# hdmi_receiver.net
KiCad netlist of a schematic drawn in EAGLE
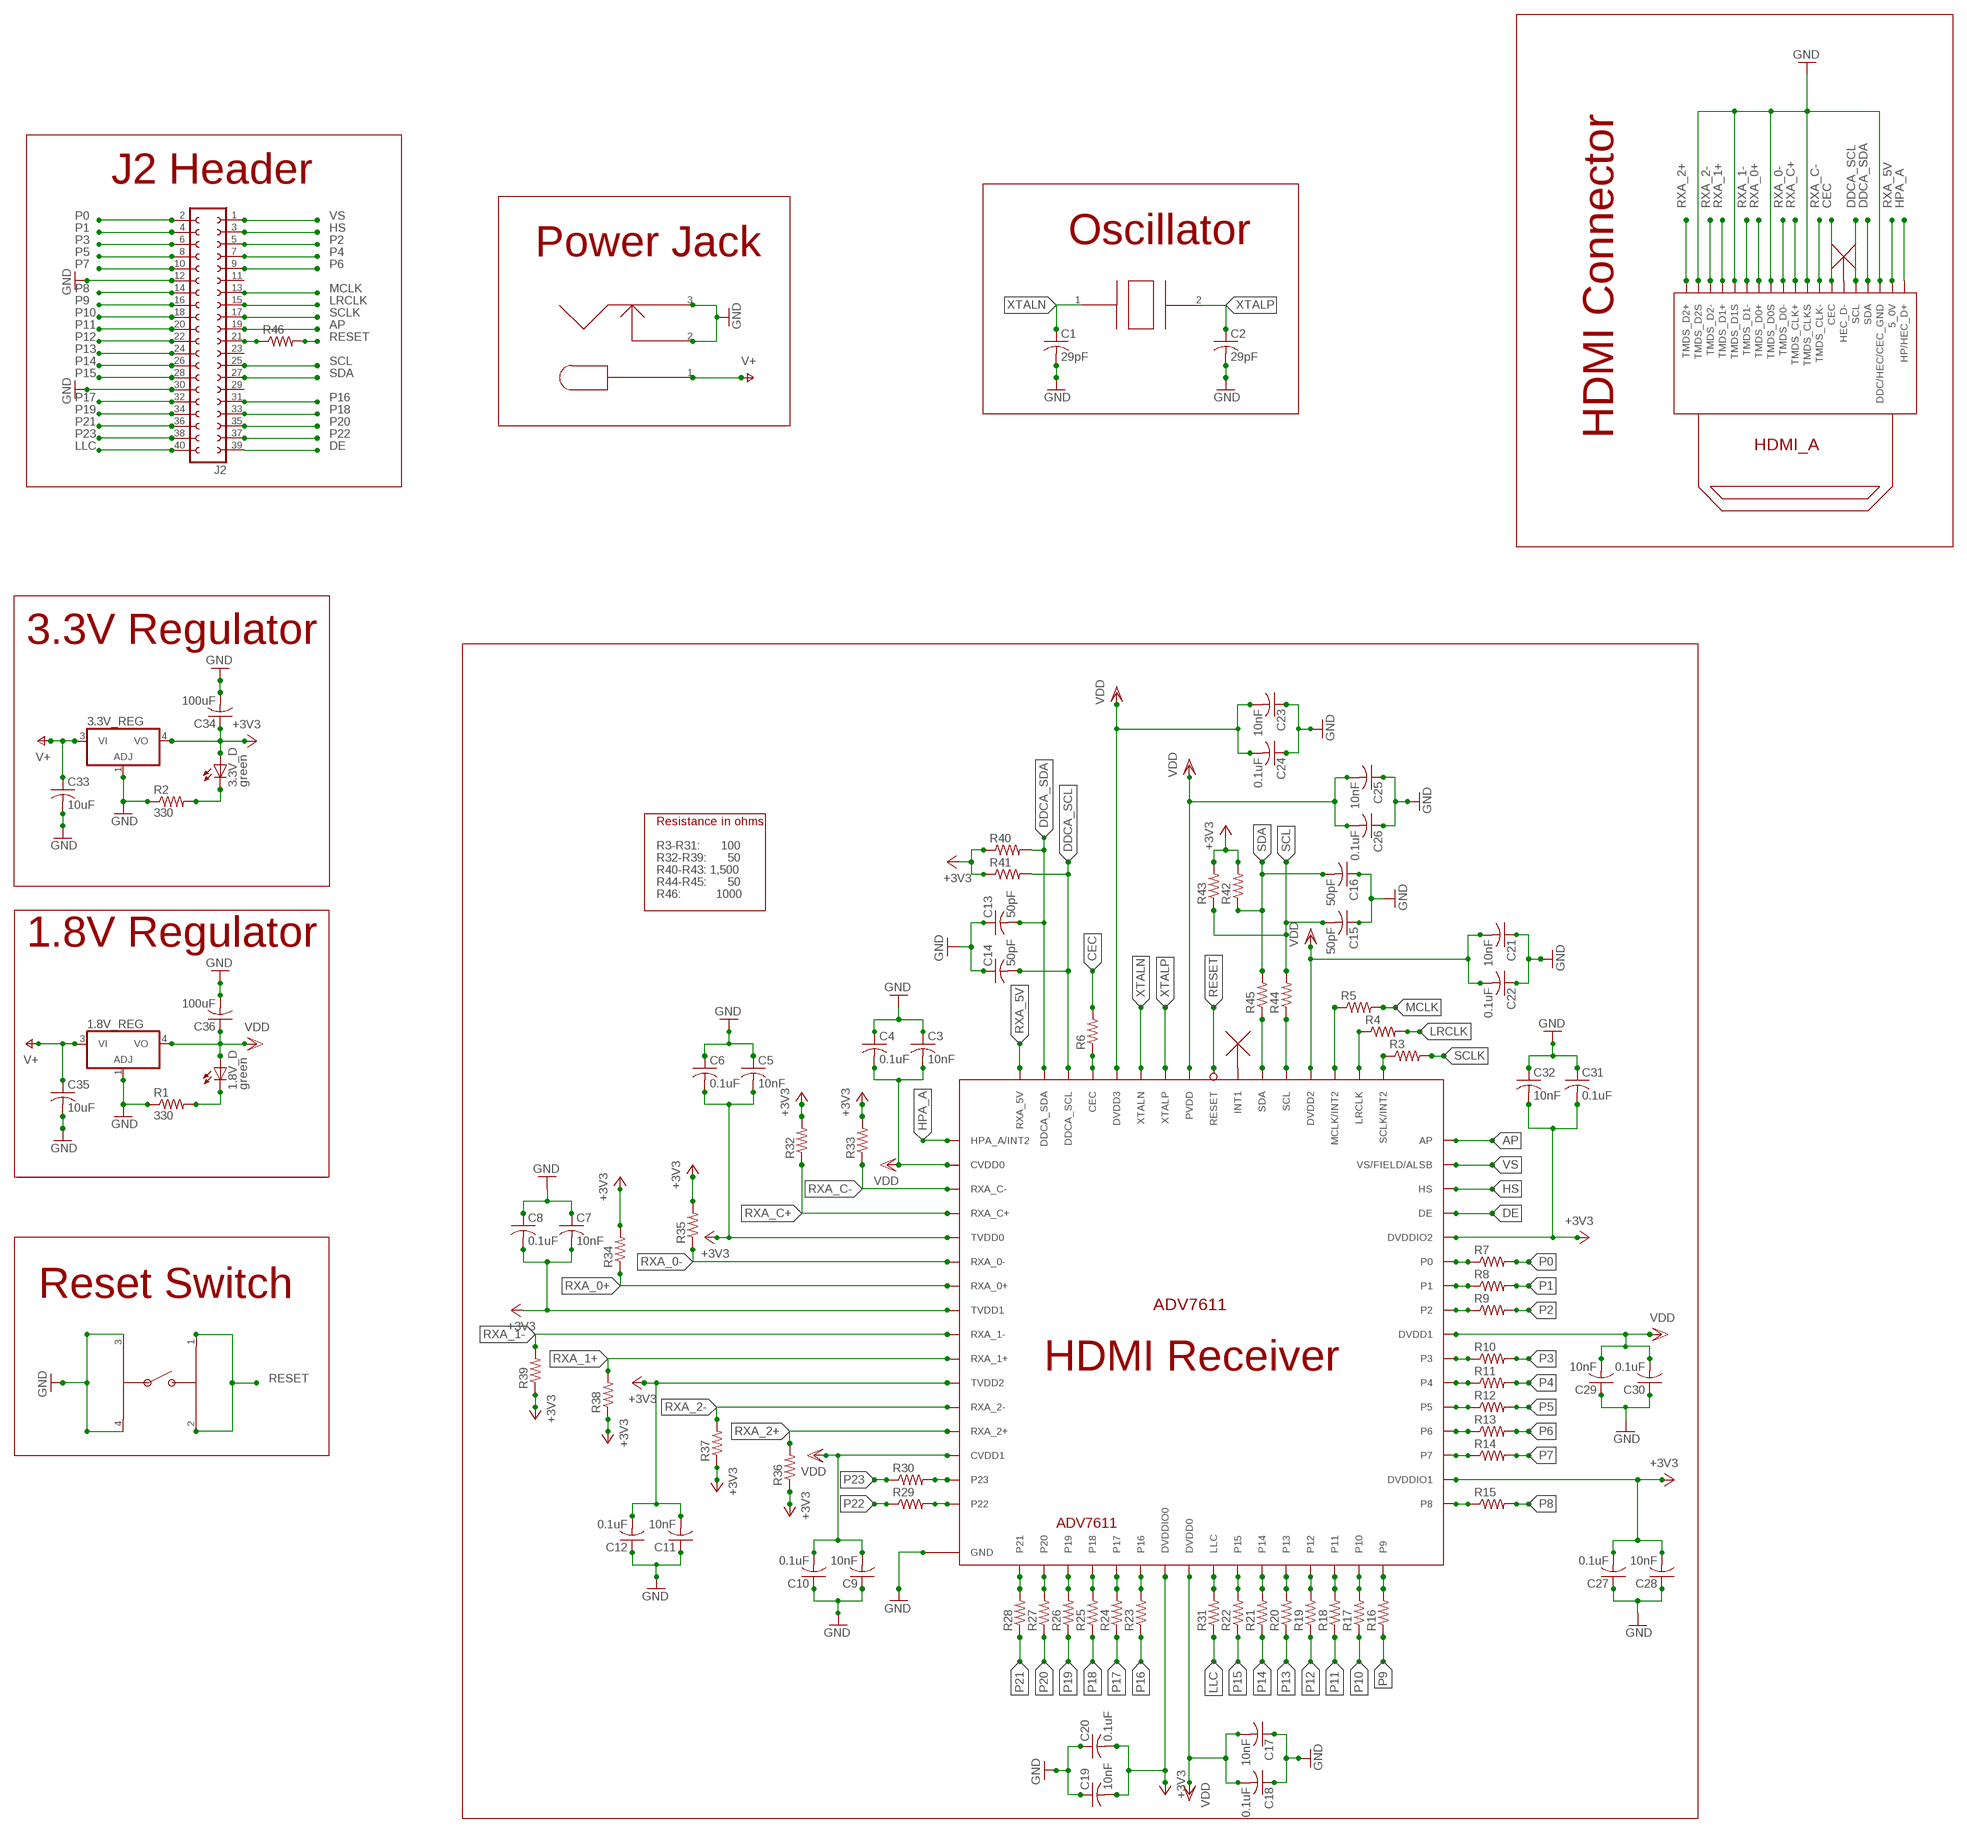
[diagram p0: schematic, sheet 1]

(export (version "E")
  (design (tool "Eeschema 10.0.6"))
  (components
    (comp (ref "1.8V_D")
      (value "green")
      (footprint "eagle-import:LED5MM")
      (libsource (lib "eagle-import") (part "LED5MM"))
    )
    (comp (ref "1.8V_REG")
      (value "317EMP")
      (footprint "eagle-import:SOT223")
      (libsource (lib "eagle-import") (part "317EMP"))
    )
    (comp (ref "3.3V_D")
      (value "green")
      (footprint "eagle-import:LED5MM")
      (libsource (lib "eagle-import") (part "LED5MM"))
    )
    (comp (ref "3.3V_REG")
      (value "317EMP")
      (footprint "eagle-import:SOT223")
      (libsource (lib "eagle-import") (part "317EMP"))
    )
    (comp (ref "ADV7611")
      (value "ADV7611")
      (footprint "eagle-import:LQFP-ST-64-2")
      (libsource (lib "eagle-import") (part "ADV7611"))
    )
    (comp (ref "C1")
      (value "29pF")
      (footprint "eagle-import:C1210")
      (libsource (lib "eagle-import") (part "C-USC1210"))
    )
    (comp (ref "C2")
      (value "29pF")
      (footprint "eagle-import:C1210")
      (libsource (lib "eagle-import") (part "C-USC1210"))
    )
    (comp (ref "C3")
      (value "10nF")
      (footprint "eagle-import:C0603")
      (libsource (lib "eagle-import") (part "C-USC0603"))
    )
    (comp (ref "C4")
      (value "0.1uF")
      (footprint "eagle-import:C0603")
      (libsource (lib "eagle-import") (part "C-USC0603"))
    )
    (comp (ref "C5")
      (value "10nF")
      (footprint "eagle-import:C0603")
      (libsource (lib "eagle-import") (part "C-USC0603"))
    )
    (comp (ref "C6")
      (value "0.1uF")
      (footprint "eagle-import:C0603")
      (libsource (lib "eagle-import") (part "C-USC0603"))
    )
    (comp (ref "C7")
      (value "10nF")
      (footprint "eagle-import:C0603")
      (libsource (lib "eagle-import") (part "C-USC0603"))
    )
    (comp (ref "C8")
      (value "0.1uF")
      (footprint "eagle-import:C0603")
      (libsource (lib "eagle-import") (part "C-USC0603"))
    )
    (comp (ref "C9")
      (value "10nF")
      (footprint "eagle-import:C0603")
      (libsource (lib "eagle-import") (part "C-USC0603"))
    )
    (comp (ref "C10")
      (value "0.1uF")
      (footprint "eagle-import:C0603")
      (libsource (lib "eagle-import") (part "C-USC0603"))
    )
    (comp (ref "C11")
      (value "10nF")
      (footprint "eagle-import:C0603")
      (libsource (lib "eagle-import") (part "C-USC0603"))
    )
    (comp (ref "C12")
      (value "0.1uF")
      (footprint "eagle-import:C0603")
      (libsource (lib "eagle-import") (part "C-USC0603"))
    )
    (comp (ref "C13")
      (value "50pF")
      (footprint "eagle-import:C0603")
      (libsource (lib "eagle-import") (part "C-USC0603"))
    )
    (comp (ref "C14")
      (value "50pF")
      (footprint "eagle-import:C0603")
      (libsource (lib "eagle-import") (part "C-USC0603"))
    )
    (comp (ref "C15")
      (value "50pF")
      (footprint "eagle-import:C0603")
      (libsource (lib "eagle-import") (part "C-USC0603"))
    )
    (comp (ref "C16")
      (value "50pF")
      (footprint "eagle-import:C0603")
      (libsource (lib "eagle-import") (part "C-USC0603"))
    )
    (comp (ref "C17")
      (value "10nF")
      (footprint "eagle-import:C0603")
      (libsource (lib "eagle-import") (part "C-USC0603"))
    )
    (comp (ref "C18")
      (value "0.1uF")
      (footprint "eagle-import:C0603")
      (libsource (lib "eagle-import") (part "C-USC0603"))
    )
    (comp (ref "C19")
      (value "10nF")
      (footprint "eagle-import:C0603")
      (libsource (lib "eagle-import") (part "C-USC0603"))
    )
    (comp (ref "C20")
      (value "0.1uF")
      (footprint "eagle-import:C0603")
      (libsource (lib "eagle-import") (part "C-USC0603"))
    )
    (comp (ref "C21")
      (value "10nF")
      (footprint "eagle-import:C0603")
      (libsource (lib "eagle-import") (part "C-USC0603"))
    )
    (comp (ref "C22")
      (value "0.1uF")
      (footprint "eagle-import:C0603")
      (libsource (lib "eagle-import") (part "C-USC0603"))
    )
    (comp (ref "C23")
      (value "10nF")
      (footprint "eagle-import:C0603")
      (libsource (lib "eagle-import") (part "C-USC0603"))
    )
    (comp (ref "C24")
      (value "0.1uF")
      (footprint "eagle-import:C0603")
      (libsource (lib "eagle-import") (part "C-USC0603"))
    )
    (comp (ref "C25")
      (value "10nF")
      (footprint "eagle-import:C0603")
      (libsource (lib "eagle-import") (part "C-USC0603"))
    )
    (comp (ref "C26")
      (value "0.1uF")
      (footprint "eagle-import:C0603")
      (libsource (lib "eagle-import") (part "C-USC0603"))
    )
    (comp (ref "C27")
      (value "0.1uF")
      (footprint "eagle-import:C0603")
      (libsource (lib "eagle-import") (part "C-USC0603"))
    )
    (comp (ref "C28")
      (value "10nF")
      (footprint "eagle-import:C0603")
      (libsource (lib "eagle-import") (part "C-USC0603"))
    )
    (comp (ref "C29")
      (value "10nF")
      (footprint "eagle-import:C0603")
      (libsource (lib "eagle-import") (part "C-USC0603"))
    )
    (comp (ref "C30")
      (value "0.1uF")
      (footprint "eagle-import:C0603")
      (libsource (lib "eagle-import") (part "C-USC0603"))
    )
    (comp (ref "C31")
      (value "0.1uF")
      (footprint "eagle-import:C0603")
      (libsource (lib "eagle-import") (part "C-USC0603"))
    )
    (comp (ref "C32")
      (value "10nF")
      (footprint "eagle-import:C0603")
      (libsource (lib "eagle-import") (part "C-USC0603"))
    )
    (comp (ref "C33")
      (value "10uF")
      (footprint "eagle-import:C0603")
      (libsource (lib "eagle-import") (part "C-USC0603"))
    )
    (comp (ref "C34")
      (value "100uF")
      (footprint "eagle-import:C1206")
      (libsource (lib "eagle-import") (part "C-USC1206"))
    )
    (comp (ref "C35")
      (value "10uF")
      (footprint "eagle-import:C0603")
      (libsource (lib "eagle-import") (part "C-USC0603"))
    )
    (comp (ref "C36")
      (value "100uF")
      (footprint "eagle-import:C1206")
      (libsource (lib "eagle-import") (part "C-USC1206"))
    )
    (comp (ref "J2")
      (value "FE20-2")
      (footprint "eagle-import:FE20-2")
      (libsource (lib "eagle-import") (part "FE20-2"))
    )
    (comp (ref "R1")
      (value "330")
      (footprint "eagle-import:R0603")
      (libsource (lib "eagle-import") (part "R-US_R0603"))
    )
    (comp (ref "R2")
      (value "330")
      (footprint "eagle-import:R0603")
      (libsource (lib "eagle-import") (part "R-US_R0603"))
    )
    (comp (ref "R3")
      (value "R-US_R0603")
      (footprint "eagle-import:R0603")
      (libsource (lib "eagle-import") (part "R-US_R0603"))
    )
    (comp (ref "R4")
      (value "R-US_R0603")
      (footprint "eagle-import:R0603")
      (libsource (lib "eagle-import") (part "R-US_R0603"))
    )
    (comp (ref "R5")
      (value "R-US_R0603")
      (footprint "eagle-import:R0603")
      (libsource (lib "eagle-import") (part "R-US_R0603"))
    )
    (comp (ref "R6")
      (value "R-US_R0603")
      (footprint "eagle-import:R0603")
      (libsource (lib "eagle-import") (part "R-US_R0603"))
    )
    (comp (ref "R7")
      (value "R-US_R0603")
      (footprint "eagle-import:R0603")
      (libsource (lib "eagle-import") (part "R-US_R0603"))
    )
    (comp (ref "R8")
      (value "R-US_R0603")
      (footprint "eagle-import:R0603")
      (libsource (lib "eagle-import") (part "R-US_R0603"))
    )
    (comp (ref "R9")
      (value "R-US_R0603")
      (footprint "eagle-import:R0603")
      (libsource (lib "eagle-import") (part "R-US_R0603"))
    )
    (comp (ref "R10")
      (value "R-US_R0603")
      (footprint "eagle-import:R0603")
      (libsource (lib "eagle-import") (part "R-US_R0603"))
    )
    (comp (ref "R11")
      (value "R-US_R0603")
      (footprint "eagle-import:R0603")
      (libsource (lib "eagle-import") (part "R-US_R0603"))
    )
    (comp (ref "R12")
      (value "R-US_R0603")
      (footprint "eagle-import:R0603")
      (libsource (lib "eagle-import") (part "R-US_R0603"))
    )
    (comp (ref "R13")
      (value "R-US_R0603")
      (footprint "eagle-import:R0603")
      (libsource (lib "eagle-import") (part "R-US_R0603"))
    )
    (comp (ref "R14")
      (value "R-US_R0603")
      (footprint "eagle-import:R0603")
      (libsource (lib "eagle-import") (part "R-US_R0603"))
    )
    (comp (ref "R15")
      (value "R-US_R0603")
      (footprint "eagle-import:R0603")
      (libsource (lib "eagle-import") (part "R-US_R0603"))
    )
    (comp (ref "R16")
      (value "R-US_R0603")
      (footprint "eagle-import:R0603")
      (libsource (lib "eagle-import") (part "R-US_R0603"))
    )
    (comp (ref "R17")
      (value "R-US_R0603")
      (footprint "eagle-import:R0603")
      (libsource (lib "eagle-import") (part "R-US_R0603"))
    )
    (comp (ref "R18")
      (value "R-US_R0603")
      (footprint "eagle-import:R0603")
      (libsource (lib "eagle-import") (part "R-US_R0603"))
    )
    (comp (ref "R19")
      (value "R-US_R0603")
      (footprint "eagle-import:R0603")
      (libsource (lib "eagle-import") (part "R-US_R0603"))
    )
    (comp (ref "R20")
      (value "R-US_R0603")
      (footprint "eagle-import:R0603")
      (libsource (lib "eagle-import") (part "R-US_R0603"))
    )
    (comp (ref "R21")
      (value "R-US_R0603")
      (footprint "eagle-import:R0603")
      (libsource (lib "eagle-import") (part "R-US_R0603"))
    )
    (comp (ref "R22")
      (value "R-US_R0603")
      (footprint "eagle-import:R0603")
      (libsource (lib "eagle-import") (part "R-US_R0603"))
    )
    (comp (ref "R23")
      (value "R-US_R0603")
      (footprint "eagle-import:R0603")
      (libsource (lib "eagle-import") (part "R-US_R0603"))
    )
    (comp (ref "R24")
      (value "R-US_R0603")
      (footprint "eagle-import:R0603")
      (libsource (lib "eagle-import") (part "R-US_R0603"))
    )
    (comp (ref "R25")
      (value "R-US_R0603")
      (footprint "eagle-import:R0603")
      (libsource (lib "eagle-import") (part "R-US_R0603"))
    )
    (comp (ref "R26")
      (value "R-US_R0603")
      (footprint "eagle-import:R0603")
      (libsource (lib "eagle-import") (part "R-US_R0603"))
    )
    (comp (ref "R27")
      (value "R-US_R0603")
      (footprint "eagle-import:R0603")
      (libsource (lib "eagle-import") (part "R-US_R0603"))
    )
    (comp (ref "R28")
      (value "R-US_R0603")
      (footprint "eagle-import:R0603")
      (libsource (lib "eagle-import") (part "R-US_R0603"))
    )
    (comp (ref "R29")
      (value "R-US_R0603")
      (footprint "eagle-import:R0603")
      (libsource (lib "eagle-import") (part "R-US_R0603"))
    )
    (comp (ref "R30")
      (value "R-US_R0603")
      (footprint "eagle-import:R0603")
      (libsource (lib "eagle-import") (part "R-US_R0603"))
    )
    (comp (ref "R31")
      (value "R-US_R0603")
      (footprint "eagle-import:R0603")
      (libsource (lib "eagle-import") (part "R-US_R0603"))
    )
    (comp (ref "R32")
      (value "R-US_R0603")
      (footprint "eagle-import:R0603")
      (libsource (lib "eagle-import") (part "R-US_R0603"))
    )
    (comp (ref "R33")
      (value "R-US_R0603")
      (footprint "eagle-import:R0603")
      (libsource (lib "eagle-import") (part "R-US_R0603"))
    )
    (comp (ref "R34")
      (value "R-US_R0603")
      (footprint "eagle-import:R0603")
      (libsource (lib "eagle-import") (part "R-US_R0603"))
    )
    (comp (ref "R35")
      (value "R-US_R0603")
      (footprint "eagle-import:R0603")
      (libsource (lib "eagle-import") (part "R-US_R0603"))
    )
    (comp (ref "R36")
      (value "R-US_R0603")
      (footprint "eagle-import:R0603")
      (libsource (lib "eagle-import") (part "R-US_R0603"))
    )
    (comp (ref "R37")
      (value "R-US_R0603")
      (footprint "eagle-import:R0603")
      (libsource (lib "eagle-import") (part "R-US_R0603"))
    )
    (comp (ref "R38")
      (value "R-US_R0603")
      (footprint "eagle-import:R0603")
      (libsource (lib "eagle-import") (part "R-US_R0603"))
    )
    (comp (ref "R39")
      (value "R-US_R0603")
      (footprint "eagle-import:R0603")
      (libsource (lib "eagle-import") (part "R-US_R0603"))
    )
    (comp (ref "R40")
      (value "R-US_R0603")
      (footprint "eagle-import:R0603")
      (libsource (lib "eagle-import") (part "R-US_R0603"))
    )
    (comp (ref "R41")
      (value "R-US_R0603")
      (footprint "eagle-import:R0603")
      (libsource (lib "eagle-import") (part "R-US_R0603"))
    )
    (comp (ref "R42")
      (value "R-US_R0603")
      (footprint "eagle-import:R0603")
      (libsource (lib "eagle-import") (part "R-US_R0603"))
    )
    (comp (ref "R43")
      (value "R-US_R0603")
      (footprint "eagle-import:R0603")
      (libsource (lib "eagle-import") (part "R-US_R0603"))
    )
    (comp (ref "R44")
      (value "R-US_R0603")
      (footprint "eagle-import:R0603")
      (libsource (lib "eagle-import") (part "R-US_R0603"))
    )
    (comp (ref "R45")
      (value "R-US_R0603")
      (footprint "eagle-import:R0603")
      (libsource (lib "eagle-import") (part "R-US_R0603"))
    )
    (comp (ref "R46")
      (value "R-US_R0603")
      (footprint "eagle-import:R0603")
      (libsource (lib "eagle-import") (part "R-US_R0603"))
    )
    (comp (ref "U$1")
      (value "111RLF")
      (footprint "eagle-import:111RLF")
      (libsource (lib "eagle-import") (part "111RLF"))
    )
    (comp (ref "U$2")
      (value "CRYSTAL_OSC")
      (footprint "eagle-import:CRYSTAL_OSC")
      (libsource (lib "eagle-import") (part "CRYSTAL_OSC"))
    )
    (comp (ref "U$3")
      (value "CK_SWITCH")
      (footprint "eagle-import:CK_SWITCH")
      (libsource (lib "eagle-import") (part "CK_SWITCH"))
    )
    (comp (ref "U$4")
      (value "DC_BARREL_CONN")
      (footprint "eagle-import:DC_BARREL_CONN")
      (libsource (lib "eagle-import") (part "DC_BARREL_CONN"))
    )
  )
  (nets
    (net (code "1") (name "+3V3") (class "Default")
      (node (ref "3.3V_D") (pin "A") (pinfunction "A_A") (pintype "passive"))
      (node (ref "3.3V_REG") (pin "4") (pinfunction "VO_4") (pintype "passive"))
      (node (ref "ADV7611") (pin "11") (pinfunction "TVDD2_11") (pintype "bidirectional"))
      (node (ref "ADV7611") (pin "23") (pinfunction "DVDDIO0_23") (pintype "bidirectional"))
      (node (ref "ADV7611") (pin "34") (pinfunction "DVDDIO1_34") (pintype "bidirectional"))
      (node (ref "ADV7611") (pin "44") (pinfunction "DVDDIO2_44") (pintype "bidirectional"))
      (node (ref "ADV7611") (pin "5") (pinfunction "TVDD0_5") (pintype "bidirectional"))
      (node (ref "ADV7611") (pin "8") (pinfunction "TVDD1_8") (pintype "bidirectional"))
      (node (ref "C11") (pin "2") (pinfunction "2_2") (pintype "passive"))
      (node (ref "C12") (pin "2") (pinfunction "2_2") (pintype "passive"))
      (node (ref "C19") (pin "2") (pinfunction "2_2") (pintype "passive"))
      (node (ref "C20") (pin "2") (pinfunction "2_2") (pintype "passive"))
      (node (ref "C27") (pin "2") (pinfunction "2_2") (pintype "passive"))
      (node (ref "C28") (pin "2") (pinfunction "2_2") (pintype "passive"))
      (node (ref "C31") (pin "2") (pinfunction "2_2") (pintype "passive"))
      (node (ref "C32") (pin "2") (pinfunction "2_2") (pintype "passive"))
      (node (ref "C34") (pin "1") (pinfunction "1_1") (pintype "passive"))
      (node (ref "C5") (pin "2") (pinfunction "2_2") (pintype "passive"))
      (node (ref "C6") (pin "2") (pinfunction "2_2") (pintype "passive"))
      (node (ref "C7") (pin "2") (pinfunction "2_2") (pintype "passive"))
      (node (ref "C8") (pin "2") (pinfunction "2_2") (pintype "passive"))
      (node (ref "R32") (pin "2") (pinfunction "2_2") (pintype "passive"))
      (node (ref "R33") (pin "2") (pinfunction "2_2") (pintype "passive"))
      (node (ref "R34") (pin "2") (pinfunction "2_2") (pintype "passive"))
      (node (ref "R35") (pin "2") (pinfunction "2_2") (pintype "passive"))
      (node (ref "R36") (pin "1") (pinfunction "1_1") (pintype "passive"))
      (node (ref "R37") (pin "1") (pinfunction "1_1") (pintype "passive"))
      (node (ref "R38") (pin "1") (pinfunction "1_1") (pintype "passive"))
      (node (ref "R39") (pin "1") (pinfunction "1_1") (pintype "passive"))
      (node (ref "R40") (pin "1") (pinfunction "1_1") (pintype "passive"))
      (node (ref "R41") (pin "1") (pinfunction "1_1") (pintype "passive"))
      (node (ref "R42") (pin "2") (pinfunction "2_2") (pintype "passive"))
      (node (ref "R43") (pin "2") (pinfunction "2_2") (pintype "passive"))
    )
    (net (code "2") (name "AP") (class "Default")
      (node (ref "ADV7611") (pin "48") (pinfunction "AP_48") (pintype "bidirectional"))
      (node (ref "J2") (pin "19") (pinfunction "19_19") (pintype "passive"))
    )
    (net (code "3") (name "CEC") (class "Default")
      (node (ref "R6") (pin "2") (pinfunction "2_2") (pintype "passive"))
      (node (ref "U$1") (pin "13") (pinfunction "CEC_13") (pintype "bidirectional"))
    )
    (net (code "4") (name "DDCA_SCL") (class "Default")
      (node (ref "ADV7611") (pin "62") (pinfunction "DDCA_SCL_62") (pintype "bidirectional"))
      (node (ref "C14") (pin "2") (pinfunction "2_2") (pintype "passive"))
      (node (ref "R41") (pin "2") (pinfunction "2_2") (pintype "passive"))
      (node (ref "U$1") (pin "15") (pinfunction "SCL_15") (pintype "bidirectional"))
    )
    (net (code "5") (name "DDCA_SDA") (class "Default")
      (node (ref "ADV7611") (pin "63") (pinfunction "DDCA_SDA_63") (pintype "bidirectional"))
      (node (ref "C13") (pin "2") (pinfunction "2_2") (pintype "passive"))
      (node (ref "R40") (pin "2") (pinfunction "2_2") (pintype "passive"))
      (node (ref "U$1") (pin "16") (pinfunction "SDA_16") (pintype "bidirectional"))
    )
    (net (code "6") (name "DE") (class "Default")
      (node (ref "ADV7611") (pin "45") (pinfunction "DE_45") (pintype "bidirectional"))
      (node (ref "J2") (pin "39") (pinfunction "39_39") (pintype "passive"))
    )
    (net (code "7") (name "GND") (class "Default")
      (node (ref "1.8V_REG") (pin "1") (pinfunction "ADJ_1") (pintype "input"))
      (node (ref "3.3V_REG") (pin "1") (pinfunction "ADJ_1") (pintype "input"))
      (node (ref "ADV7611") (pin "0") (pinfunction "GND_0") (pintype "bidirectional"))
      (node (ref "C1") (pin "2") (pinfunction "2_2") (pintype "passive"))
      (node (ref "C10") (pin "1") (pinfunction "1_1") (pintype "passive"))
      (node (ref "C11") (pin "1") (pinfunction "1_1") (pintype "passive"))
      (node (ref "C12") (pin "1") (pinfunction "1_1") (pintype "passive"))
      (node (ref "C13") (pin "1") (pinfunction "1_1") (pintype "passive"))
      (node (ref "C14") (pin "1") (pinfunction "1_1") (pintype "passive"))
      (node (ref "C15") (pin "1") (pinfunction "1_1") (pintype "passive"))
      (node (ref "C16") (pin "1") (pinfunction "1_1") (pintype "passive"))
      (node (ref "C17") (pin "1") (pinfunction "1_1") (pintype "passive"))
      (node (ref "C18") (pin "1") (pinfunction "1_1") (pintype "passive"))
      (node (ref "C19") (pin "1") (pinfunction "1_1") (pintype "passive"))
      (node (ref "C2") (pin "2") (pinfunction "2_2") (pintype "passive"))
      (node (ref "C20") (pin "1") (pinfunction "1_1") (pintype "passive"))
      (node (ref "C21") (pin "1") (pinfunction "1_1") (pintype "passive"))
      (node (ref "C22") (pin "1") (pinfunction "1_1") (pintype "passive"))
      (node (ref "C23") (pin "1") (pinfunction "1_1") (pintype "passive"))
      (node (ref "C24") (pin "1") (pinfunction "1_1") (pintype "passive"))
      (node (ref "C25") (pin "1") (pinfunction "1_1") (pintype "passive"))
      (node (ref "C26") (pin "1") (pinfunction "1_1") (pintype "passive"))
      (node (ref "C27") (pin "1") (pinfunction "1_1") (pintype "passive"))
      (node (ref "C28") (pin "1") (pinfunction "1_1") (pintype "passive"))
      (node (ref "C29") (pin "1") (pinfunction "1_1") (pintype "passive"))
      (node (ref "C3") (pin "1") (pinfunction "1_1") (pintype "passive"))
      (node (ref "C30") (pin "1") (pinfunction "1_1") (pintype "passive"))
      (node (ref "C31") (pin "1") (pinfunction "1_1") (pintype "passive"))
      (node (ref "C32") (pin "1") (pinfunction "1_1") (pintype "passive"))
      (node (ref "C33") (pin "2") (pinfunction "2_2") (pintype "passive"))
      (node (ref "C34") (pin "2") (pinfunction "2_2") (pintype "passive"))
      (node (ref "C35") (pin "2") (pinfunction "2_2") (pintype "passive"))
      (node (ref "C36") (pin "2") (pinfunction "2_2") (pintype "passive"))
      (node (ref "C4") (pin "1") (pinfunction "1_1") (pintype "passive"))
      (node (ref "C5") (pin "1") (pinfunction "1_1") (pintype "passive"))
      (node (ref "C6") (pin "1") (pinfunction "1_1") (pintype "passive"))
      (node (ref "C7") (pin "1") (pinfunction "1_1") (pintype "passive"))
      (node (ref "C8") (pin "1") (pinfunction "1_1") (pintype "passive"))
      (node (ref "C9") (pin "1") (pinfunction "1_1") (pintype "passive"))
      (node (ref "J2") (pin "12") (pinfunction "12_12") (pintype "passive"))
      (node (ref "J2") (pin "30") (pinfunction "30_30") (pintype "passive"))
      (node (ref "R1") (pin "1") (pinfunction "1_1") (pintype "passive"))
      (node (ref "R2") (pin "1") (pinfunction "1_1") (pintype "passive"))
      (node (ref "U$1") (pin "11") (pinfunction "TMDS_CLKS_11") (pintype "bidirectional"))
      (node (ref "U$1") (pin "17") (pinfunction "DDC/HEC/CEC_GND_17") (pintype "bidirectional"))
      (node (ref "U$1") (pin "2") (pinfunction "TMDS_D2S_2") (pintype "bidirectional"))
      (node (ref "U$1") (pin "5") (pinfunction "TMDS_D1S_5") (pintype "bidirectional"))
      (node (ref "U$1") (pin "8") (pinfunction "TMDS_D0S_8") (pintype "bidirectional"))
      (node (ref "U$3") (pin "3") (pinfunction "3_3") (pintype "bidirectional"))
      (node (ref "U$3") (pin "4") (pinfunction "4_4") (pintype "bidirectional"))
      (node (ref "U$4") (pin "2") (pinfunction "2_2") (pintype "bidirectional"))
      (node (ref "U$4") (pin "3") (pinfunction "3_3") (pintype "bidirectional"))
    )
    (net (code "8") (name "HPA_A") (class "Default")
      (node (ref "ADV7611") (pin "1") (pinfunction "HPA_A/INT2_1") (pintype "bidirectional"))
      (node (ref "U$1") (pin "19") (pinfunction "HP/HEC_D+_19") (pintype "bidirectional"))
    )
    (net (code "9") (name "HS") (class "Default")
      (node (ref "ADV7611") (pin "46") (pinfunction "HS_46") (pintype "bidirectional"))
      (node (ref "J2") (pin "3") (pinfunction "3_3") (pintype "passive"))
    )
    (net (code "10") (name "LLC") (class "Default")
      (node (ref "J2") (pin "40") (pinfunction "40_40") (pintype "passive"))
      (node (ref "R31") (pin "1") (pinfunction "1_1") (pintype "passive"))
    )
    (net (code "11") (name "LRCLK") (class "Default")
      (node (ref "J2") (pin "15") (pinfunction "15_15") (pintype "passive"))
      (node (ref "R4") (pin "2") (pinfunction "2_2") (pintype "passive"))
    )
    (net (code "12") (name "MCLK") (class "Default")
      (node (ref "J2") (pin "13") (pinfunction "13_13") (pintype "passive"))
      (node (ref "R5") (pin "2") (pinfunction "2_2") (pintype "passive"))
    )
    (net (code "13") (name "Net-(1.8V_D-C)") (class "Default")
      (node (ref "1.8V_D") (pin "K") (pinfunction "C_K") (pintype "passive"))
      (node (ref "R1") (pin "2") (pinfunction "2_2") (pintype "passive"))
    )
    (net (code "14") (name "Net-(3.3V_D-C)") (class "Default")
      (node (ref "3.3V_D") (pin "K") (pinfunction "C_K") (pintype "passive"))
      (node (ref "R2") (pin "2") (pinfunction "2_2") (pintype "passive"))
    )
    (net (code "15") (name "Net-(ADV7611-CEC)") (class "Default")
      (node (ref "ADV7611") (pin "61") (pinfunction "CEC_61") (pintype "bidirectional"))
      (node (ref "R6") (pin "1") (pinfunction "1_1") (pintype "passive"))
    )
    (net (code "16") (name "Net-(ADV7611-LLC)") (class "Default")
      (node (ref "ADV7611") (pin "25") (pinfunction "LLC_25") (pintype "bidirectional"))
      (node (ref "R31") (pin "2") (pinfunction "2_2") (pintype "passive"))
    )
    (net (code "17") (name "Net-(ADV7611-LRCLK)") (class "Default")
      (node (ref "ADV7611") (pin "50") (pinfunction "LRCLK_50") (pintype "bidirectional"))
      (node (ref "R4") (pin "1") (pinfunction "1_1") (pintype "passive"))
    )
    (net (code "18") (name "Net-(ADV7611-MCLK{slash}INT2)") (class "Default")
      (node (ref "ADV7611") (pin "51") (pinfunction "MCLK/INT2_51") (pintype "bidirectional"))
      (node (ref "R5") (pin "1") (pinfunction "1_1") (pintype "passive"))
    )
    (net (code "19") (name "Net-(ADV7611-P0)") (class "Default")
      (node (ref "ADV7611") (pin "43") (pinfunction "P0_43") (pintype "bidirectional"))
      (node (ref "R7") (pin "1") (pinfunction "1_1") (pintype "passive"))
    )
    (net (code "20") (name "Net-(ADV7611-P1)") (class "Default")
      (node (ref "ADV7611") (pin "42") (pinfunction "P1_42") (pintype "bidirectional"))
      (node (ref "R8") (pin "1") (pinfunction "1_1") (pintype "passive"))
    )
    (net (code "21") (name "Net-(ADV7611-P2)") (class "Default")
      (node (ref "ADV7611") (pin "41") (pinfunction "P2_41") (pintype "bidirectional"))
      (node (ref "R9") (pin "1") (pinfunction "1_1") (pintype "passive"))
    )
    (net (code "22") (name "Net-(ADV7611-P3)") (class "Default")
      (node (ref "ADV7611") (pin "39") (pinfunction "P3_39") (pintype "bidirectional"))
      (node (ref "R10") (pin "1") (pinfunction "1_1") (pintype "passive"))
    )
    (net (code "23") (name "Net-(ADV7611-P4)") (class "Default")
      (node (ref "ADV7611") (pin "38") (pinfunction "P4_38") (pintype "bidirectional"))
      (node (ref "R11") (pin "1") (pinfunction "1_1") (pintype "passive"))
    )
    (net (code "24") (name "Net-(ADV7611-P5)") (class "Default")
      (node (ref "ADV7611") (pin "37") (pinfunction "P5_37") (pintype "bidirectional"))
      (node (ref "R12") (pin "1") (pinfunction "1_1") (pintype "passive"))
    )
    (net (code "25") (name "Net-(ADV7611-P6)") (class "Default")
      (node (ref "ADV7611") (pin "36") (pinfunction "P6_36") (pintype "bidirectional"))
      (node (ref "R13") (pin "1") (pinfunction "1_1") (pintype "passive"))
    )
    (net (code "26") (name "Net-(ADV7611-P7)") (class "Default")
      (node (ref "ADV7611") (pin "35") (pinfunction "P7_35") (pintype "bidirectional"))
      (node (ref "R14") (pin "1") (pinfunction "1_1") (pintype "passive"))
    )
    (net (code "27") (name "Net-(ADV7611-P8)") (class "Default")
      (node (ref "ADV7611") (pin "33") (pinfunction "P8_33") (pintype "bidirectional"))
      (node (ref "R15") (pin "1") (pinfunction "1_1") (pintype "passive"))
    )
    (net (code "28") (name "Net-(ADV7611-P9)") (class "Default")
      (node (ref "ADV7611") (pin "32") (pinfunction "P9_32") (pintype "bidirectional"))
      (node (ref "R16") (pin "2") (pinfunction "2_2") (pintype "passive"))
    )
    (net (code "29") (name "Net-(ADV7611-P10)") (class "Default")
      (node (ref "ADV7611") (pin "31") (pinfunction "P10_31") (pintype "bidirectional"))
      (node (ref "R17") (pin "2") (pinfunction "2_2") (pintype "passive"))
    )
    (net (code "30") (name "Net-(ADV7611-P11)") (class "Default")
      (node (ref "ADV7611") (pin "30") (pinfunction "P11_30") (pintype "bidirectional"))
      (node (ref "R18") (pin "2") (pinfunction "2_2") (pintype "passive"))
    )
    (net (code "31") (name "Net-(ADV7611-P12)") (class "Default")
      (node (ref "ADV7611") (pin "29") (pinfunction "P12_29") (pintype "bidirectional"))
      (node (ref "R19") (pin "2") (pinfunction "2_2") (pintype "passive"))
    )
    (net (code "32") (name "Net-(ADV7611-P13)") (class "Default")
      (node (ref "ADV7611") (pin "28") (pinfunction "P13_28") (pintype "bidirectional"))
      (node (ref "R20") (pin "2") (pinfunction "2_2") (pintype "passive"))
    )
    (net (code "33") (name "Net-(ADV7611-P14)") (class "Default")
      (node (ref "ADV7611") (pin "27") (pinfunction "P14_27") (pintype "bidirectional"))
      (node (ref "R21") (pin "2") (pinfunction "2_2") (pintype "passive"))
    )
    (net (code "34") (name "Net-(ADV7611-P15)") (class "Default")
      (node (ref "ADV7611") (pin "26") (pinfunction "P15_26") (pintype "bidirectional"))
      (node (ref "R22") (pin "2") (pinfunction "2_2") (pintype "passive"))
    )
    (net (code "35") (name "Net-(ADV7611-P16)") (class "Default")
      (node (ref "ADV7611") (pin "22") (pinfunction "P16_22") (pintype "bidirectional"))
      (node (ref "R23") (pin "2") (pinfunction "2_2") (pintype "passive"))
    )
    (net (code "36") (name "Net-(ADV7611-P17)") (class "Default")
      (node (ref "ADV7611") (pin "21") (pinfunction "P17_21") (pintype "bidirectional"))
      (node (ref "R24") (pin "2") (pinfunction "2_2") (pintype "passive"))
    )
    (net (code "37") (name "Net-(ADV7611-P18)") (class "Default")
      (node (ref "ADV7611") (pin "20") (pinfunction "P18_20") (pintype "bidirectional"))
      (node (ref "R25") (pin "2") (pinfunction "2_2") (pintype "passive"))
    )
    (net (code "38") (name "Net-(ADV7611-P19)") (class "Default")
      (node (ref "ADV7611") (pin "19") (pinfunction "P19_19") (pintype "bidirectional"))
      (node (ref "R26") (pin "2") (pinfunction "2_2") (pintype "passive"))
    )
    (net (code "39") (name "Net-(ADV7611-P20)") (class "Default")
      (node (ref "ADV7611") (pin "18") (pinfunction "P20_18") (pintype "bidirectional"))
      (node (ref "R27") (pin "2") (pinfunction "2_2") (pintype "passive"))
    )
    (net (code "40") (name "Net-(ADV7611-P21)") (class "Default")
      (node (ref "ADV7611") (pin "17") (pinfunction "P21_17") (pintype "bidirectional"))
      (node (ref "R28") (pin "2") (pinfunction "2_2") (pintype "passive"))
    )
    (net (code "41") (name "Net-(ADV7611-P22)") (class "Default")
      (node (ref "ADV7611") (pin "16") (pinfunction "P22_16") (pintype "bidirectional"))
      (node (ref "R29") (pin "2") (pinfunction "2_2") (pintype "passive"))
    )
    (net (code "42") (name "Net-(ADV7611-P23)") (class "Default")
      (node (ref "ADV7611") (pin "15") (pinfunction "P23_15") (pintype "bidirectional"))
      (node (ref "R30") (pin "2") (pinfunction "2_2") (pintype "passive"))
    )
    (net (code "43") (name "Net-(ADV7611-SCL)") (class "Default")
      (node (ref "ADV7611") (pin "53") (pinfunction "SCL_53") (pintype "bidirectional"))
      (node (ref "R44") (pin "1") (pinfunction "1_1") (pintype "passive"))
    )
    (net (code "44") (name "Net-(ADV7611-SCLK{slash}INT2)") (class "Default")
      (node (ref "ADV7611") (pin "49") (pinfunction "SCLK/INT2_49") (pintype "bidirectional"))
      (node (ref "R3") (pin "1") (pinfunction "1_1") (pintype "passive"))
    )
    (net (code "45") (name "Net-(ADV7611-SDA)") (class "Default")
      (node (ref "ADV7611") (pin "54") (pinfunction "SDA_54") (pintype "bidirectional"))
      (node (ref "R45") (pin "1") (pinfunction "1_1") (pintype "passive"))
    )
    (net (code "46") (name "Net-(J2-Pad21)") (class "Default")
      (node (ref "J2") (pin "21") (pinfunction "21_21") (pintype "passive"))
      (node (ref "R46") (pin "1") (pinfunction "1_1") (pintype "passive"))
    )
    (net (code "47") (name "P0") (class "Default")
      (node (ref "J2") (pin "2") (pinfunction "2_2") (pintype "passive"))
      (node (ref "R7") (pin "2") (pinfunction "2_2") (pintype "passive"))
    )
    (net (code "48") (name "P1") (class "Default")
      (node (ref "J2") (pin "4") (pinfunction "4_4") (pintype "passive"))
      (node (ref "R8") (pin "2") (pinfunction "2_2") (pintype "passive"))
    )
    (net (code "49") (name "P2") (class "Default")
      (node (ref "J2") (pin "5") (pinfunction "5_5") (pintype "passive"))
      (node (ref "R9") (pin "2") (pinfunction "2_2") (pintype "passive"))
    )
    (net (code "50") (name "P3") (class "Default")
      (node (ref "J2") (pin "6") (pinfunction "6_6") (pintype "passive"))
      (node (ref "R10") (pin "2") (pinfunction "2_2") (pintype "passive"))
    )
    (net (code "51") (name "P4") (class "Default")
      (node (ref "J2") (pin "7") (pinfunction "7_7") (pintype "passive"))
      (node (ref "R11") (pin "2") (pinfunction "2_2") (pintype "passive"))
    )
    (net (code "52") (name "P5") (class "Default")
      (node (ref "J2") (pin "8") (pinfunction "8_8") (pintype "passive"))
      (node (ref "R12") (pin "2") (pinfunction "2_2") (pintype "passive"))
    )
    (net (code "53") (name "P6") (class "Default")
      (node (ref "J2") (pin "9") (pinfunction "9_9") (pintype "passive"))
      (node (ref "R13") (pin "2") (pinfunction "2_2") (pintype "passive"))
    )
    (net (code "54") (name "P7") (class "Default")
      (node (ref "J2") (pin "10") (pinfunction "10_10") (pintype "passive"))
      (node (ref "R14") (pin "2") (pinfunction "2_2") (pintype "passive"))
    )
    (net (code "55") (name "P8") (class "Default")
      (node (ref "J2") (pin "14") (pinfunction "14_14") (pintype "passive"))
      (node (ref "R15") (pin "2") (pinfunction "2_2") (pintype "passive"))
    )
    (net (code "56") (name "P9") (class "Default")
      (node (ref "J2") (pin "16") (pinfunction "16_16") (pintype "passive"))
      (node (ref "R16") (pin "1") (pinfunction "1_1") (pintype "passive"))
    )
    (net (code "57") (name "P10") (class "Default")
      (node (ref "J2") (pin "18") (pinfunction "18_18") (pintype "passive"))
      (node (ref "R17") (pin "1") (pinfunction "1_1") (pintype "passive"))
    )
    (net (code "58") (name "P11") (class "Default")
      (node (ref "J2") (pin "20") (pinfunction "20_20") (pintype "passive"))
      (node (ref "R18") (pin "1") (pinfunction "1_1") (pintype "passive"))
    )
    (net (code "59") (name "P12") (class "Default")
      (node (ref "J2") (pin "22") (pinfunction "22_22") (pintype "passive"))
      (node (ref "R19") (pin "1") (pinfunction "1_1") (pintype "passive"))
    )
    (net (code "60") (name "P13") (class "Default")
      (node (ref "J2") (pin "24") (pinfunction "24_24") (pintype "passive"))
      (node (ref "R20") (pin "1") (pinfunction "1_1") (pintype "passive"))
    )
    (net (code "61") (name "P14") (class "Default")
      (node (ref "J2") (pin "26") (pinfunction "26_26") (pintype "passive"))
      (node (ref "R21") (pin "1") (pinfunction "1_1") (pintype "passive"))
    )
    (net (code "62") (name "P15") (class "Default")
      (node (ref "J2") (pin "28") (pinfunction "28_28") (pintype "passive"))
      (node (ref "R22") (pin "1") (pinfunction "1_1") (pintype "passive"))
    )
    (net (code "63") (name "P16") (class "Default")
      (node (ref "J2") (pin "31") (pinfunction "31_31") (pintype "passive"))
      (node (ref "R23") (pin "1") (pinfunction "1_1") (pintype "passive"))
    )
    (net (code "64") (name "P17") (class "Default")
      (node (ref "J2") (pin "32") (pinfunction "32_32") (pintype "passive"))
      (node (ref "R24") (pin "1") (pinfunction "1_1") (pintype "passive"))
    )
    (net (code "65") (name "P18") (class "Default")
      (node (ref "J2") (pin "33") (pinfunction "33_33") (pintype "passive"))
      (node (ref "R25") (pin "1") (pinfunction "1_1") (pintype "passive"))
    )
    (net (code "66") (name "P19") (class "Default")
      (node (ref "J2") (pin "34") (pinfunction "34_34") (pintype "passive"))
      (node (ref "R26") (pin "1") (pinfunction "1_1") (pintype "passive"))
    )
    (net (code "67") (name "P20") (class "Default")
      (node (ref "J2") (pin "35") (pinfunction "35_35") (pintype "passive"))
      (node (ref "R27") (pin "1") (pinfunction "1_1") (pintype "passive"))
    )
    (net (code "68") (name "P21") (class "Default")
      (node (ref "J2") (pin "36") (pinfunction "36_36") (pintype "passive"))
      (node (ref "R28") (pin "1") (pinfunction "1_1") (pintype "passive"))
    )
    (net (code "69") (name "P22") (class "Default")
      (node (ref "J2") (pin "37") (pinfunction "37_37") (pintype "passive"))
      (node (ref "R29") (pin "1") (pinfunction "1_1") (pintype "passive"))
    )
    (net (code "70") (name "P23") (class "Default")
      (node (ref "J2") (pin "38") (pinfunction "38_38") (pintype "passive"))
      (node (ref "R30") (pin "1") (pinfunction "1_1") (pintype "passive"))
    )
    (net (code "71") (name "RESET") (class "Default")
      (node (ref "ADV7611") (pin "56") (pinfunction "RESET_56") (pintype "bidirectional"))
      (node (ref "R46") (pin "2") (pinfunction "2_2") (pintype "passive"))
      (node (ref "U$3") (pin "1") (pinfunction "1_1") (pintype "bidirectional"))
      (node (ref "U$3") (pin "2") (pinfunction "2_2") (pintype "bidirectional"))
    )
    (net (code "72") (name "RXA_0+") (class "Default")
      (node (ref "ADV7611") (pin "7") (pinfunction "RXA_0+_7") (pintype "bidirectional"))
      (node (ref "R34") (pin "1") (pinfunction "1_1") (pintype "passive"))
      (node (ref "U$1") (pin "7") (pinfunction "TMDS_D0+_7") (pintype "bidirectional"))
    )
    (net (code "73") (name "RXA_0-") (class "Default")
      (node (ref "ADV7611") (pin "6") (pinfunction "RXA_0-_6") (pintype "bidirectional"))
      (node (ref "R35") (pin "1") (pinfunction "1_1") (pintype "passive"))
      (node (ref "U$1") (pin "9") (pinfunction "TMDS_D0-_9") (pintype "bidirectional"))
    )
    (net (code "74") (name "RXA_1+") (class "Default")
      (node (ref "ADV7611") (pin "10") (pinfunction "RXA_1+_10") (pintype "bidirectional"))
      (node (ref "R38") (pin "2") (pinfunction "2_2") (pintype "passive"))
      (node (ref "U$1") (pin "4") (pinfunction "TMDS_D1+_4") (pintype "bidirectional"))
    )
    (net (code "75") (name "RXA_1-") (class "Default")
      (node (ref "ADV7611") (pin "9") (pinfunction "RXA_1-_9") (pintype "bidirectional"))
      (node (ref "R39") (pin "2") (pinfunction "2_2") (pintype "passive"))
      (node (ref "U$1") (pin "6") (pinfunction "TMDS_D1-_6") (pintype "bidirectional"))
    )
    (net (code "76") (name "RXA_2+") (class "Default")
      (node (ref "ADV7611") (pin "13") (pinfunction "RXA_2+_13") (pintype "bidirectional"))
      (node (ref "R36") (pin "2") (pinfunction "2_2") (pintype "passive"))
      (node (ref "U$1") (pin "1") (pinfunction "TMDS_D2+_1") (pintype "bidirectional"))
    )
    (net (code "77") (name "RXA_2-") (class "Default")
      (node (ref "ADV7611") (pin "12") (pinfunction "RXA_2-_12") (pintype "bidirectional"))
      (node (ref "R37") (pin "2") (pinfunction "2_2") (pintype "passive"))
      (node (ref "U$1") (pin "3") (pinfunction "TMDS_D2-_3") (pintype "bidirectional"))
    )
    (net (code "78") (name "RXA_5V") (class "Default")
      (node (ref "ADV7611") (pin "64") (pinfunction "RXA_5V_64") (pintype "bidirectional"))
      (node (ref "U$1") (pin "18") (pinfunction "5_0V_18") (pintype "bidirectional"))
    )
    (net (code "79") (name "RXA_C+") (class "Default")
      (node (ref "ADV7611") (pin "4") (pinfunction "RXA_C+_4") (pintype "bidirectional"))
      (node (ref "R32") (pin "1") (pinfunction "1_1") (pintype "passive"))
      (node (ref "U$1") (pin "10") (pinfunction "TMDS_CLK+_10") (pintype "bidirectional"))
    )
    (net (code "80") (name "RXA_C-") (class "Default")
      (node (ref "ADV7611") (pin "3") (pinfunction "RXA_C-_3") (pintype "bidirectional"))
      (node (ref "R33") (pin "1") (pinfunction "1_1") (pintype "passive"))
      (node (ref "U$1") (pin "12") (pinfunction "TMDS_CLK-_12") (pintype "bidirectional"))
    )
    (net (code "81") (name "SCL") (class "Default")
      (node (ref "C15") (pin "2") (pinfunction "2_2") (pintype "passive"))
      (node (ref "J2") (pin "25") (pinfunction "25_25") (pintype "passive"))
      (node (ref "R43") (pin "1") (pinfunction "1_1") (pintype "passive"))
      (node (ref "R44") (pin "2") (pinfunction "2_2") (pintype "passive"))
    )
    (net (code "82") (name "SCLK") (class "Default")
      (node (ref "J2") (pin "17") (pinfunction "17_17") (pintype "passive"))
      (node (ref "R3") (pin "2") (pinfunction "2_2") (pintype "passive"))
    )
    (net (code "83") (name "SDA") (class "Default")
      (node (ref "C16") (pin "2") (pinfunction "2_2") (pintype "passive"))
      (node (ref "J2") (pin "27") (pinfunction "27_27") (pintype "passive"))
      (node (ref "R42") (pin "1") (pinfunction "1_1") (pintype "passive"))
      (node (ref "R45") (pin "2") (pinfunction "2_2") (pintype "passive"))
    )
    (net (code "84") (name "V+") (class "Default")
      (node (ref "1.8V_REG") (pin "3") (pinfunction "VI_3") (pintype "input"))
      (node (ref "3.3V_REG") (pin "3") (pinfunction "VI_3") (pintype "input"))
      (node (ref "C33") (pin "1") (pinfunction "1_1") (pintype "passive"))
      (node (ref "C35") (pin "1") (pinfunction "1_1") (pintype "passive"))
      (node (ref "U$4") (pin "1") (pinfunction "1_1") (pintype "bidirectional"))
    )
    (net (code "85") (name "VDD") (class "Default")
      (node (ref "1.8V_D") (pin "A") (pinfunction "A_A") (pintype "passive"))
      (node (ref "1.8V_REG") (pin "4") (pinfunction "VO_4") (pintype "passive"))
      (node (ref "ADV7611") (pin "14") (pinfunction "CVDD1_14") (pintype "bidirectional"))
      (node (ref "ADV7611") (pin "2") (pinfunction "CVDD0_2") (pintype "bidirectional"))
      (node (ref "ADV7611") (pin "24") (pinfunction "DVDD0_24") (pintype "bidirectional"))
      (node (ref "ADV7611") (pin "40") (pinfunction "DVDD1_40") (pintype "bidirectional"))
      (node (ref "ADV7611") (pin "52") (pinfunction "DVDD2_52") (pintype "bidirectional"))
      (node (ref "ADV7611") (pin "57") (pinfunction "PVDD_57") (pintype "bidirectional"))
      (node (ref "ADV7611") (pin "60") (pinfunction "DVDD3_60") (pintype "bidirectional"))
      (node (ref "C10") (pin "2") (pinfunction "2_2") (pintype "passive"))
      (node (ref "C17") (pin "2") (pinfunction "2_2") (pintype "passive"))
      (node (ref "C18") (pin "2") (pinfunction "2_2") (pintype "passive"))
      (node (ref "C21") (pin "2") (pinfunction "2_2") (pintype "passive"))
      (node (ref "C22") (pin "2") (pinfunction "2_2") (pintype "passive"))
      (node (ref "C23") (pin "2") (pinfunction "2_2") (pintype "passive"))
      (node (ref "C24") (pin "2") (pinfunction "2_2") (pintype "passive"))
      (node (ref "C25") (pin "2") (pinfunction "2_2") (pintype "passive"))
      (node (ref "C26") (pin "2") (pinfunction "2_2") (pintype "passive"))
      (node (ref "C29") (pin "2") (pinfunction "2_2") (pintype "passive"))
      (node (ref "C3") (pin "2") (pinfunction "2_2") (pintype "passive"))
      (node (ref "C30") (pin "2") (pinfunction "2_2") (pintype "passive"))
      (node (ref "C36") (pin "1") (pinfunction "1_1") (pintype "passive"))
      (node (ref "C4") (pin "2") (pinfunction "2_2") (pintype "passive"))
      (node (ref "C9") (pin "2") (pinfunction "2_2") (pintype "passive"))
    )
    (net (code "86") (name "VS") (class "Default")
      (node (ref "ADV7611") (pin "47") (pinfunction "VS/FIELD/ALSB_47") (pintype "bidirectional"))
      (node (ref "J2") (pin "1") (pinfunction "1_1") (pintype "passive"))
    )
    (net (code "87") (name "XTALN") (class "Default")
      (node (ref "ADV7611") (pin "59") (pinfunction "XTALN_59") (pintype "bidirectional"))
      (node (ref "C1") (pin "1") (pinfunction "1_1") (pintype "passive"))
      (node (ref "U$2") (pin "1") (pinfunction "1_1") (pintype "bidirectional"))
    )
    (net (code "88") (name "XTALP") (class "Default")
      (node (ref "ADV7611") (pin "58") (pinfunction "XTALP_58") (pintype "bidirectional"))
      (node (ref "C2") (pin "1") (pinfunction "1_1") (pintype "passive"))
      (node (ref "U$2") (pin "2") (pinfunction "2_2") (pintype "bidirectional"))
    )
    (net (code "89") (name "unconnected-(ADV7611-INT1-Pad55)") (class "Default")
      (node (ref "ADV7611") (pin "55") (pinfunction "INT1_55") (pintype "bidirectional"))
    )
    (net (code "90") (name "unconnected-(J2-Pad11)") (class "Default")
      (node (ref "J2") (pin "11") (pinfunction "11_11") (pintype "passive"))
    )
    (net (code "91") (name "unconnected-(J2-Pad23)") (class "Default")
      (node (ref "J2") (pin "23") (pinfunction "23_23") (pintype "passive"))
    )
    (net (code "92") (name "unconnected-(J2-Pad29)") (class "Default")
      (node (ref "J2") (pin "29") (pinfunction "29_29") (pintype "passive"))
    )
    (net (code "93") (name "unconnected-(U$1-HEC_D--Pad14)") (class "Default")
      (node (ref "U$1") (pin "14") (pinfunction "HEC_D-_14") (pintype "bidirectional"))
    )
  )
)
